# MXP_power.net
KiCad netlist of a schematic drawn in EAGLE
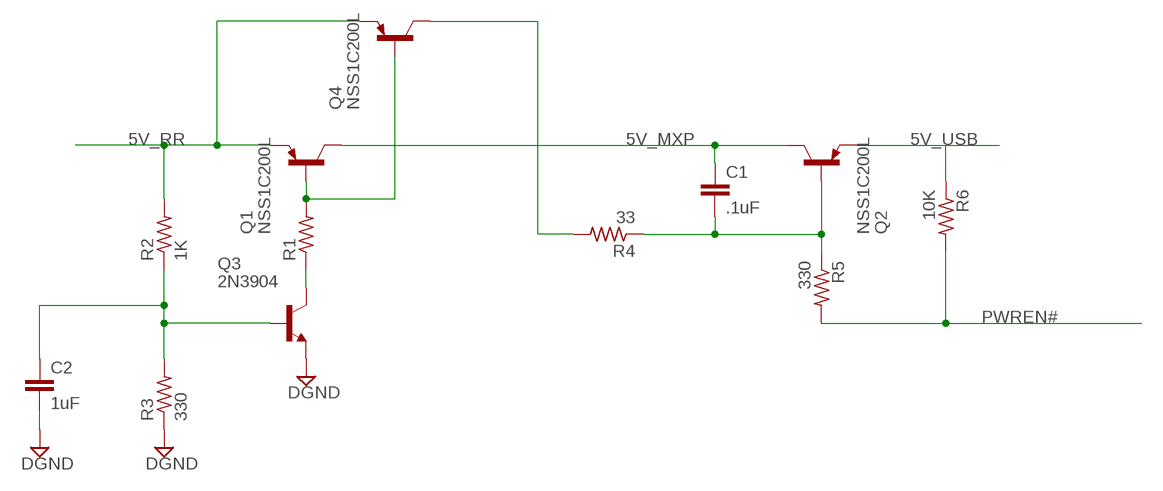
[diagram p0: schematic, sheet 1]

(export (version "E")
  (design (tool "Eeschema 10.0.6"))
  (components
    (comp (ref "C1")
      (value ".1uF")
      (footprint "eagle-import:C2.5-3")
      (libsource (lib "eagle-import") (part "C2,5-3"))
    )
    (comp (ref "C2")
      (value "1uF")
      (footprint "eagle-import:C2.5-3")
      (libsource (lib "eagle-import") (part "C2,5-3"))
    )
    (comp (ref "Q1")
      (value "NSS1C200L")
      (footprint "eagle-import:TO220")
      (libsource (lib "eagle-import") (part "TIP30"))
    )
    (comp (ref "Q2")
      (value "NSS1C200L")
      (footprint "eagle-import:TO220")
      (libsource (lib "eagle-import") (part "TIP30"))
    )
    (comp (ref "Q3")
      (value "2N3904")
      (footprint "eagle-import:TO92")
      (libsource (lib "eagle-import") (part "2N3904"))
    )
    (comp (ref "Q4")
      (value "NSS1C200L")
      (footprint "eagle-import:TO220")
      (libsource (lib "eagle-import") (part "TIP30"))
    )
    (comp (ref "R1")
      (value "R-US_R0603")
      (footprint "eagle-import:R0603")
      (libsource (lib "eagle-import") (part "R-US_R0603"))
    )
    (comp (ref "R2")
      (value "1K")
      (footprint "eagle-import:R0603")
      (libsource (lib "eagle-import") (part "R-US_R0603"))
    )
    (comp (ref "R3")
      (value "330")
      (footprint "eagle-import:R0603")
      (libsource (lib "eagle-import") (part "R-US_R0603"))
    )
    (comp (ref "R4")
      (value "33")
      (footprint "eagle-import:R0603")
      (libsource (lib "eagle-import") (part "R-US_R0603"))
    )
    (comp (ref "R5")
      (value "330")
      (footprint "eagle-import:R0603")
      (libsource (lib "eagle-import") (part "R-US_R0603"))
    )
    (comp (ref "R6")
      (value "10K")
      (footprint "eagle-import:R0603")
      (libsource (lib "eagle-import") (part "R-US_R0603"))
    )
  )
  (nets
    (net (code "1") (name "/5V_MXP") (class "Default")
      (node (ref "C1") (pin "1") (pinfunction "1_1") (pintype "passive"))
      (node (ref "Q1") (pin "2") (pinfunction "C_2") (pintype "passive"))
      (node (ref "Q2") (pin "2") (pinfunction "C_2") (pintype "passive"))
    )
    (net (code "2") (name "/5V_RR") (class "Default")
      (node (ref "Q1") (pin "3") (pinfunction "E_3") (pintype "passive"))
      (node (ref "Q4") (pin "3") (pinfunction "E_3") (pintype "passive"))
      (node (ref "R2") (pin "2") (pinfunction "2_2") (pintype "passive"))
    )
    (net (code "3") (name "/5V_USB") (class "Default")
      (node (ref "Q2") (pin "3") (pinfunction "E_3") (pintype "passive"))
      (node (ref "R6") (pin "1") (pinfunction "1_1") (pintype "passive"))
    )
    (net (code "4") (name "/PWREN#") (class "Default")
      (node (ref "R5") (pin "2") (pinfunction "2_2") (pintype "passive"))
      (node (ref "R6") (pin "2") (pinfunction "2_2") (pintype "passive"))
    )
    (net (code "5") (name "DGND") (class "Default")
      (node (ref "C2") (pin "2") (pinfunction "2_2") (pintype "passive"))
      (node (ref "Q3") (pin "3") (pinfunction "E_3") (pintype "passive"))
      (node (ref "R3") (pin "1") (pinfunction "1_1") (pintype "passive"))
    )
    (net (code "6") (name "Net-(Q1-B)") (class "Default")
      (node (ref "Q1") (pin "1") (pinfunction "B_1") (pintype "passive"))
      (node (ref "Q4") (pin "1") (pinfunction "B_1") (pintype "passive"))
      (node (ref "R1") (pin "2") (pinfunction "2_2") (pintype "passive"))
    )
    (net (code "7") (name "Net-(Q2-B)") (class "Default")
      (node (ref "C1") (pin "2") (pinfunction "2_2") (pintype "passive"))
      (node (ref "Q2") (pin "1") (pinfunction "B_1") (pintype "passive"))
      (node (ref "R4") (pin "1") (pinfunction "1_1") (pintype "passive"))
      (node (ref "R5") (pin "1") (pinfunction "1_1") (pintype "passive"))
    )
    (net (code "8") (name "Net-(Q3-B)") (class "Default")
      (node (ref "C2") (pin "1") (pinfunction "1_1") (pintype "passive"))
      (node (ref "Q3") (pin "2") (pinfunction "B_2") (pintype "passive"))
      (node (ref "R2") (pin "1") (pinfunction "1_1") (pintype "passive"))
      (node (ref "R3") (pin "2") (pinfunction "2_2") (pintype "passive"))
    )
    (net (code "9") (name "Net-(Q3-C)") (class "Default")
      (node (ref "Q3") (pin "1") (pinfunction "C_1") (pintype "passive"))
      (node (ref "R1") (pin "1") (pinfunction "1_1") (pintype "passive"))
    )
    (net (code "10") (name "Net-(Q4-C)") (class "Default")
      (node (ref "Q4") (pin "2") (pinfunction "C_2") (pintype "passive"))
      (node (ref "R4") (pin "2") (pinfunction "2_2") (pintype "passive"))
    )
  )
)
